# button2.net
KiCad netlist of a schematic drawn in Altium Designer
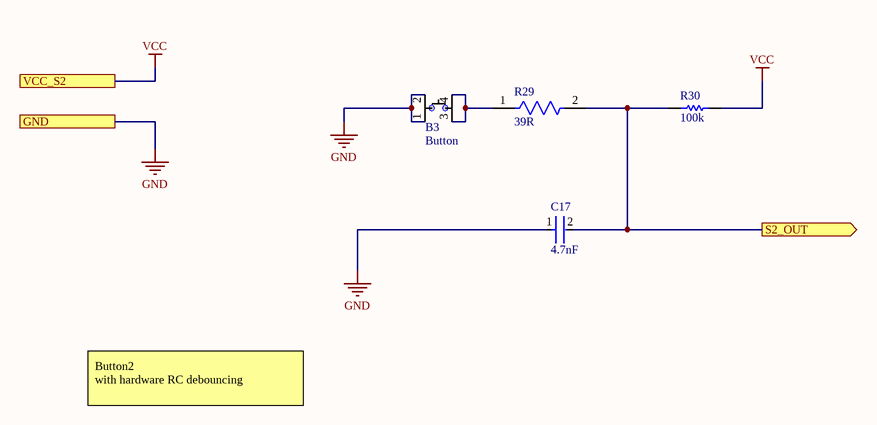
[diagram p0: button2.SchDoc]

(export (version "E")
  (design (tool "Eeschema 10.0.6"))
  (components
    (comp (ref "B3")
      (value "Button")
      (footprint "PTS810 SJK 250 SMTR LFS")
      (description "SWITCH TACTILE SPST-NO 0.05A 16V Tactile Switch SPST-NO Top Actuated Surface Mount")
      (fields
        (field (name "MANUFACTURER") "ITT /  C&K Components")
        (field (name "MANUFACTURER PART NUMBER") "PTS810SJK250SMTRLFS")
      )
      (libsource (lib "Schematics") (part "PTS810 SJK 250 SMTR LFS"))
    )
    (comp (ref "C17")
      (value "4.7nF")
      (footprint "FP-0603-L_1_6_0_15-W_0_81-MFG")
      (description "General Purpose Ceramic Capacitor, 0603, 4.7nF, 10%, X7R, 15%, 50V")
      (fields (field (name "VOLTAGE") "50V") (field (name "TOLERANCE") "10%"))
      (libsource (lib "Altium Content Vault") (part "02cd4be3c70576c341d710602a673aa"))
    )
    (comp (ref "R29")
      (value "39R")
      (footprint "FP-CPF0603-MFG")
      (description "RES SMD 39Ω 0.1% 1/16W 0603")
      (fields
        (field (name "TOLERANCE") "0.1%")
        (field (name "OCTOPART") "https://octopart.com/cpf0603b39re1-te+connectivity-9539401")
      )
      (libsource (lib "Altium Content Vault") (part "1029c3af85768c4190bb7ad29bc67b5"))
    )
    (comp (ref "R30")
      (value "100k")
      (footprint "RESC1609X55X30ML10T20")
      (fields (field (name "MANUFACTURER") "Vishay Dale") (field (name "PART NUMBER") "TNPW0603100KBEEA"))
      (libsource (lib "Altium Content Vault") (part "RES"))
    )
  )
  (nets
    (net (code "1") (name "/S2_OUT") (class "Default")
      (node (ref "C17") (pin "2") (pinfunction "2_2") (pintype "passive"))
      (node (ref "R29") (pin "2") (pinfunction "2_2") (pintype "passive"))
      (node (ref "R30") (pin "1") (pinfunction "1_1") (pintype "passive"))
    )
    (net (code "2") (name "GND") (class "Default")
      (node (ref "B3") (pin "1") (pinfunction "1_1") (pintype "power_in"))
      (node (ref "B3") (pin "2") (pinfunction "2_2") (pintype "power_in"))
      (node (ref "C17") (pin "1") (pinfunction "1_1") (pintype "passive"))
    )
    (net (code "3") (name "Net-(B3-Pad3)") (class "Default")
      (node (ref "B3") (pin "3") (pinfunction "3_3") (pintype "power_in"))
      (node (ref "B3") (pin "4") (pinfunction "4_4") (pintype "power_in"))
      (node (ref "R29") (pin "1") (pinfunction "1_1") (pintype "passive"))
    )
    (net (code "4") (name "VCC") (class "Default")
      (node (ref "R30") (pin "2") (pinfunction "2_2") (pintype "passive"))
    )
  )
)
